# io_board.net
KiCad netlist of a schematic drawn in EAGLE
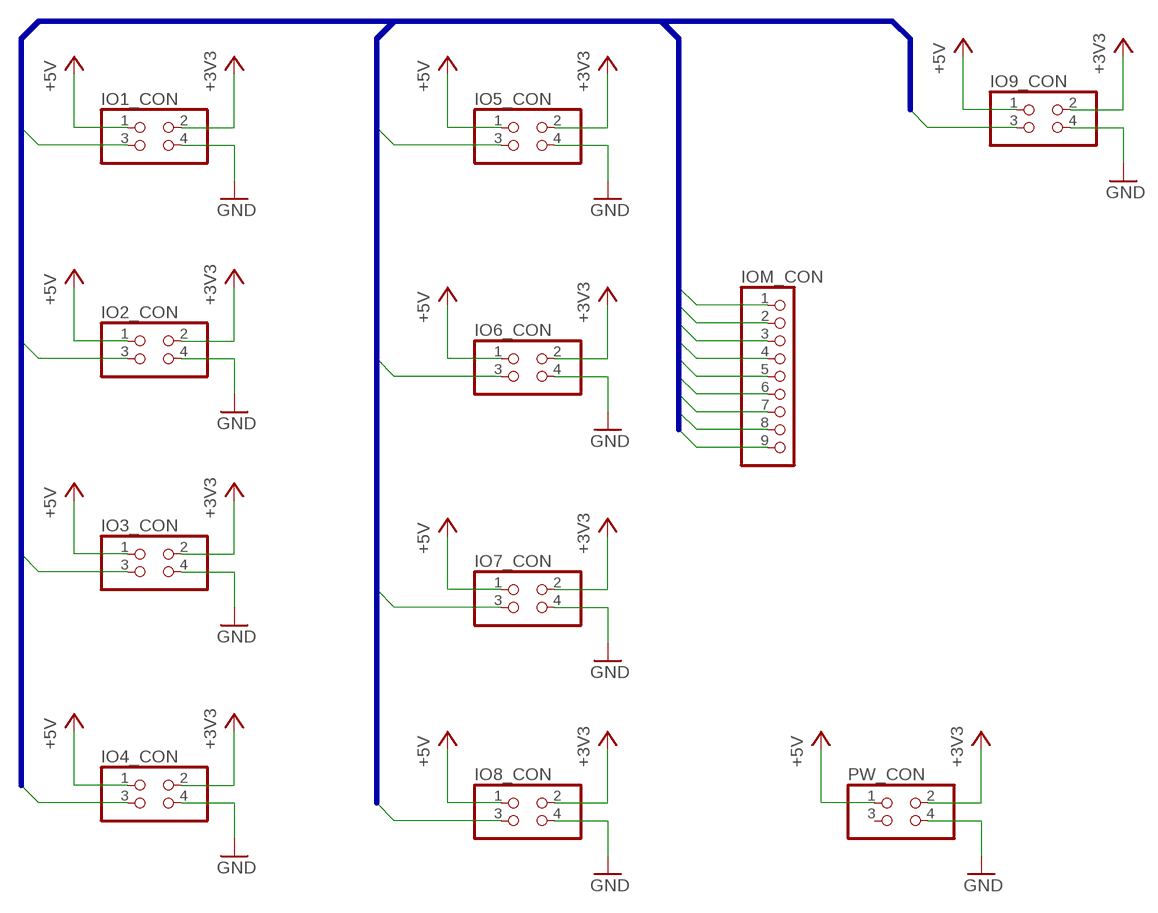
[diagram p0: schematic, sheet 1]

(export (version "E")
  (design (tool "Eeschema 10.0.6"))
  (components
    (comp (ref "IO1_CON")
      (value "PINHD-2X2")
      (footprint "eagle-import:2X02")
      (libsource (lib "eagle-import") (part "PINHD-2X2"))
    )
    (comp (ref "IO2_CON")
      (value "PINHD-2X2")
      (footprint "eagle-import:2X02")
      (libsource (lib "eagle-import") (part "PINHD-2X2"))
    )
    (comp (ref "IO3_CON")
      (value "PINHD-2X2")
      (footprint "eagle-import:2X02")
      (libsource (lib "eagle-import") (part "PINHD-2X2"))
    )
    (comp (ref "IO4_CON")
      (value "PINHD-2X2")
      (footprint "eagle-import:2X02")
      (libsource (lib "eagle-import") (part "PINHD-2X2"))
    )
    (comp (ref "IO5_CON")
      (value "PINHD-2X2")
      (footprint "eagle-import:2X02")
      (libsource (lib "eagle-import") (part "PINHD-2X2"))
    )
    (comp (ref "IO6_CON")
      (value "PINHD-2X2")
      (footprint "eagle-import:2X02")
      (libsource (lib "eagle-import") (part "PINHD-2X2"))
    )
    (comp (ref "IO7_CON")
      (value "PINHD-2X2")
      (footprint "eagle-import:2X02")
      (libsource (lib "eagle-import") (part "PINHD-2X2"))
    )
    (comp (ref "IO8_CON")
      (value "PINHD-2X2")
      (footprint "eagle-import:2X02")
      (libsource (lib "eagle-import") (part "PINHD-2X2"))
    )
    (comp (ref "IO9_CON")
      (value "PINHD-2X2")
      (footprint "eagle-import:2X02")
      (libsource (lib "eagle-import") (part "PINHD-2X2"))
    )
    (comp (ref "IOM_CON")
      (value "PINHD-1X9")
      (footprint "eagle-import:1X09")
      (libsource (lib "eagle-import") (part "PINHD-1X9"))
    )
    (comp (ref "PW_CON")
      (value "PINHD-2X2")
      (footprint "eagle-import:2X02")
      (libsource (lib "eagle-import") (part "PINHD-2X2"))
    )
  )
  (nets
    (net (code "1") (name "+3V3") (class "Default")
      (node (ref "IO1_CON") (pin "2") (pinfunction "2_2") (pintype "passive"))
      (node (ref "IO2_CON") (pin "2") (pinfunction "2_2") (pintype "passive"))
      (node (ref "IO3_CON") (pin "2") (pinfunction "2_2") (pintype "passive"))
      (node (ref "IO4_CON") (pin "2") (pinfunction "2_2") (pintype "passive"))
      (node (ref "IO5_CON") (pin "2") (pinfunction "2_2") (pintype "passive"))
      (node (ref "IO6_CON") (pin "2") (pinfunction "2_2") (pintype "passive"))
      (node (ref "IO7_CON") (pin "2") (pinfunction "2_2") (pintype "passive"))
      (node (ref "IO8_CON") (pin "2") (pinfunction "2_2") (pintype "passive"))
      (node (ref "IO9_CON") (pin "2") (pinfunction "2_2") (pintype "passive"))
      (node (ref "PW_CON") (pin "2") (pinfunction "2_2") (pintype "passive"))
    )
    (net (code "2") (name "+5V") (class "Default")
      (node (ref "IO1_CON") (pin "1") (pinfunction "1_1") (pintype "passive"))
      (node (ref "IO2_CON") (pin "1") (pinfunction "1_1") (pintype "passive"))
      (node (ref "IO3_CON") (pin "1") (pinfunction "1_1") (pintype "passive"))
      (node (ref "IO4_CON") (pin "1") (pinfunction "1_1") (pintype "passive"))
      (node (ref "IO5_CON") (pin "1") (pinfunction "1_1") (pintype "passive"))
      (node (ref "IO6_CON") (pin "1") (pinfunction "1_1") (pintype "passive"))
      (node (ref "IO7_CON") (pin "1") (pinfunction "1_1") (pintype "passive"))
      (node (ref "IO8_CON") (pin "1") (pinfunction "1_1") (pintype "passive"))
      (node (ref "IO9_CON") (pin "1") (pinfunction "1_1") (pintype "passive"))
      (node (ref "PW_CON") (pin "1") (pinfunction "1_1") (pintype "passive"))
    )
    (net (code "3") (name "/IO0") (class "Default")
      (node (ref "IO1_CON") (pin "3") (pinfunction "3_3") (pintype "passive"))
      (node (ref "IOM_CON") (pin "1") (pinfunction "1_1") (pintype "passive"))
    )
    (net (code "4") (name "/IO1") (class "Default")
      (node (ref "IO2_CON") (pin "3") (pinfunction "3_3") (pintype "passive"))
      (node (ref "IOM_CON") (pin "2") (pinfunction "2_2") (pintype "passive"))
    )
    (net (code "5") (name "/IO2") (class "Default")
      (node (ref "IO3_CON") (pin "3") (pinfunction "3_3") (pintype "passive"))
      (node (ref "IOM_CON") (pin "3") (pinfunction "3_3") (pintype "passive"))
    )
    (net (code "6") (name "/IO3") (class "Default")
      (node (ref "IO4_CON") (pin "3") (pinfunction "3_3") (pintype "passive"))
      (node (ref "IOM_CON") (pin "4") (pinfunction "4_4") (pintype "passive"))
    )
    (net (code "7") (name "/IO4") (class "Default")
      (node (ref "IO5_CON") (pin "3") (pinfunction "3_3") (pintype "passive"))
      (node (ref "IOM_CON") (pin "5") (pinfunction "5_5") (pintype "passive"))
    )
    (net (code "8") (name "/IO5") (class "Default")
      (node (ref "IO6_CON") (pin "3") (pinfunction "3_3") (pintype "passive"))
      (node (ref "IOM_CON") (pin "6") (pinfunction "6_6") (pintype "passive"))
    )
    (net (code "9") (name "/IO6") (class "Default")
      (node (ref "IO7_CON") (pin "3") (pinfunction "3_3") (pintype "passive"))
      (node (ref "IOM_CON") (pin "7") (pinfunction "7_7") (pintype "passive"))
    )
    (net (code "10") (name "/IO7") (class "Default")
      (node (ref "IO8_CON") (pin "3") (pinfunction "3_3") (pintype "passive"))
      (node (ref "IOM_CON") (pin "8") (pinfunction "8_8") (pintype "passive"))
    )
    (net (code "11") (name "/IO8") (class "Default")
      (node (ref "IO9_CON") (pin "3") (pinfunction "3_3") (pintype "passive"))
      (node (ref "IOM_CON") (pin "9") (pinfunction "9_9") (pintype "passive"))
    )
    (net (code "12") (name "GND") (class "Default")
      (node (ref "IO1_CON") (pin "4") (pinfunction "4_4") (pintype "passive"))
      (node (ref "IO2_CON") (pin "4") (pinfunction "4_4") (pintype "passive"))
      (node (ref "IO3_CON") (pin "4") (pinfunction "4_4") (pintype "passive"))
      (node (ref "IO4_CON") (pin "4") (pinfunction "4_4") (pintype "passive"))
      (node (ref "IO5_CON") (pin "4") (pinfunction "4_4") (pintype "passive"))
      (node (ref "IO6_CON") (pin "4") (pinfunction "4_4") (pintype "passive"))
      (node (ref "IO7_CON") (pin "4") (pinfunction "4_4") (pintype "passive"))
      (node (ref "IO8_CON") (pin "4") (pinfunction "4_4") (pintype "passive"))
      (node (ref "IO9_CON") (pin "4") (pinfunction "4_4") (pintype "passive"))
      (node (ref "PW_CON") (pin "4") (pinfunction "4_4") (pintype "passive"))
    )
    (net (code "13") (name "unconnected-(PW_CON-Pad3)") (class "Default")
      (node (ref "PW_CON") (pin "3") (pinfunction "3_3") (pintype "passive"))
    )
  )
)
